# Mini_Power_Supply.net
KiCad netlist of a schematic drawn in EAGLE
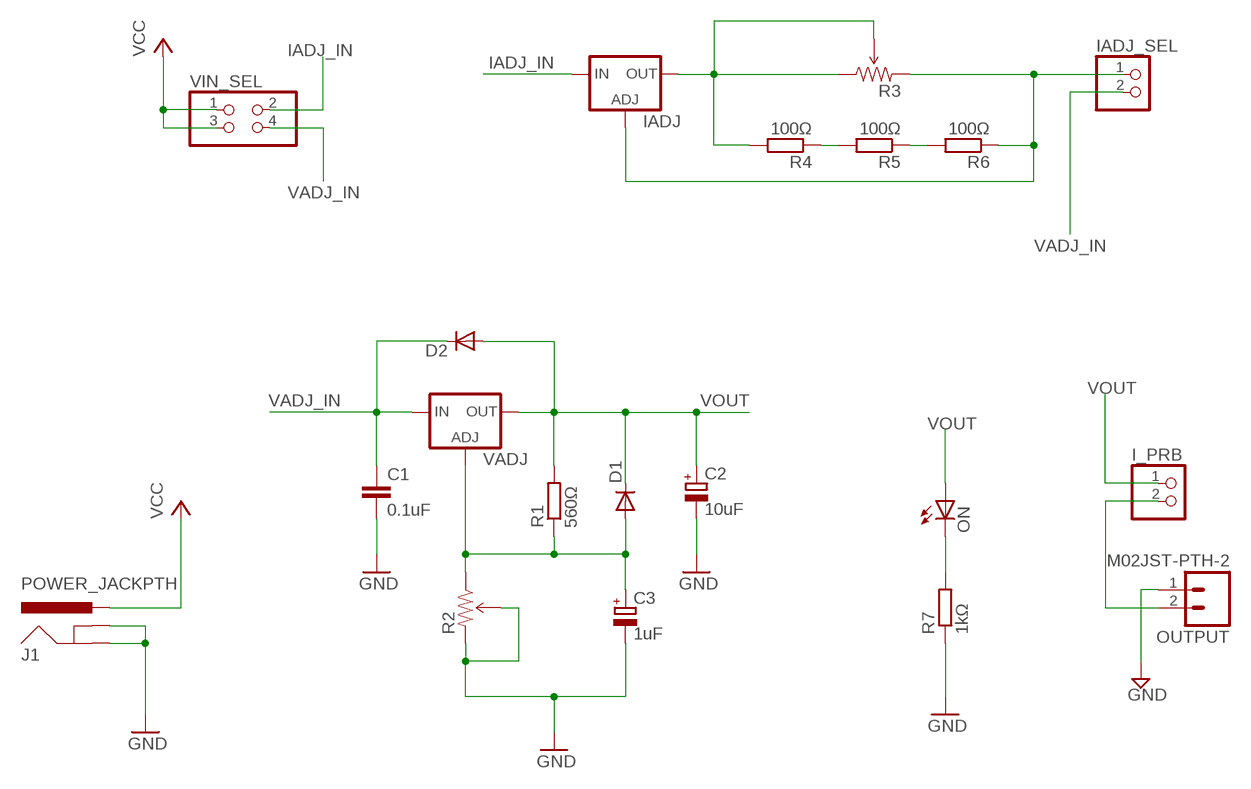
[diagram p0: schematic, sheet 1]

(export (version "E")
  (design (tool "Eeschema 10.0.6"))
  (components
    (comp (ref "C1")
      (value "0.1uF")
      (footprint "eagle-import:C0805")
      (libsource (lib "eagle-import") (part "C-EUC0805"))
    )
    (comp (ref "C2")
      (value "10uF")
      (footprint "eagle-import:E2,5-6")
      (libsource (lib "eagle-import") (part "CPOL-EUE2.5-6"))
    )
    (comp (ref "C3")
      (value "1uF")
      (footprint "eagle-import:E2,5-6")
      (libsource (lib "eagle-import") (part "CPOL-EUE2.5-6"))
    )
    (comp (ref "D1")
      (value "DIODE-SOD323-W")
      (footprint "eagle-import:SOD323-W")
      (libsource (lib "eagle-import") (part "DIODE-SOD323-W"))
    )
    (comp (ref "D2")
      (value "DIODE-SOD323-W")
      (footprint "eagle-import:SOD323-W")
      (libsource (lib "eagle-import") (part "DIODE-SOD323-W"))
    )
    (comp (ref "IADJ")
      (value "LM317TS")
      (footprint "eagle-import:317TS")
      (libsource (lib "eagle-import") (part "LM317TS"))
    )
    (comp (ref "IADJ_SEL")
      (value "PINHD-1X2")
      (footprint "eagle-import:1X02")
      (libsource (lib "eagle-import") (part "PINHD-1X2"))
    )
    (comp (ref "I_PRB")
      (value "PINHD-1X2")
      (footprint "eagle-import:1X02")
      (libsource (lib "eagle-import") (part "PINHD-1X2"))
    )
    (comp (ref "J1")
      (value "POWER_JACKPTH")
      (footprint "eagle-import:POWER_JACK_PTH")
      (libsource (lib "eagle-import") (part "POWER_JACKPTH"))
    )
    (comp (ref "ON")
      (value "LEDCHIPLED_1206")
      (footprint "eagle-import:CHIPLED_1206")
      (libsource (lib "eagle-import") (part "LEDCHIPLED_1206"))
    )
    (comp (ref "OUTPUT")
      (value "M02JST-PTH-2")
      (footprint "eagle-import:JST-2-PTH")
      (libsource (lib "eagle-import") (part "M02JST-PTH-2"))
    )
    (comp (ref "R1")
      (value "560Ω")
      (footprint "eagle-import:R0805")
      (libsource (lib "eagle-import") (part "R-EU_R0805"))
    )
    (comp (ref "R2")
      (value "TRIMPOT-PTH-KNOB")
      (footprint "eagle-import:3386U")
      (libsource (lib "eagle-import") (part "TRIMPOT-PTH-KNOB"))
    )
    (comp (ref "R3")
      (value "TRIMPOT-PTH-KNOB")
      (footprint "eagle-import:3386U")
      (libsource (lib "eagle-import") (part "TRIMPOT-PTH-KNOB"))
    )
    (comp (ref "R4")
      (value "100Ω")
      (footprint "eagle-import:R0805")
      (libsource (lib "eagle-import") (part "R-EU_R0805"))
    )
    (comp (ref "R5")
      (value "100Ω")
      (footprint "eagle-import:R0805")
      (libsource (lib "eagle-import") (part "R-EU_R0805"))
    )
    (comp (ref "R6")
      (value "100Ω")
      (footprint "eagle-import:R0805")
      (libsource (lib "eagle-import") (part "R-EU_R0805"))
    )
    (comp (ref "R7")
      (value "1kΩ")
      (footprint "eagle-import:R0805")
      (libsource (lib "eagle-import") (part "R-EU_R0805"))
    )
    (comp (ref "VADJ")
      (value "LM317TS")
      (footprint "eagle-import:317TS")
      (libsource (lib "eagle-import") (part "LM317TS"))
    )
    (comp (ref "VIN_SEL")
      (value "PINHD-2X2")
      (footprint "eagle-import:2X02")
      (libsource (lib "eagle-import") (part "PINHD-2X2"))
    )
  )
  (nets
    (net (code "1") (name "/IADJ_IN") (class "Default")
      (node (ref "IADJ") (pin "3") (pinfunction "IN_3") (pintype "input"))
      (node (ref "VIN_SEL") (pin "2") (pinfunction "2_2") (pintype "passive"))
    )
    (net (code "2") (name "/VADJ_IN") (class "Default")
      (node (ref "C1") (pin "1") (pinfunction "1_1") (pintype "passive"))
      (node (ref "D2") (pin "C") (pinfunction "C_C") (pintype "passive"))
      (node (ref "IADJ_SEL") (pin "2") (pinfunction "2_2") (pintype "passive"))
      (node (ref "VADJ") (pin "3") (pinfunction "IN_3") (pintype "input"))
      (node (ref "VIN_SEL") (pin "4") (pinfunction "4_4") (pintype "passive"))
    )
    (net (code "3") (name "/VOUT") (class "Default")
      (node (ref "C2") (pin "+") (pinfunction "+_+") (pintype "passive"))
      (node (ref "D1") (pin "C") (pinfunction "C_C") (pintype "passive"))
      (node (ref "D2") (pin "A") (pinfunction "A_A") (pintype "passive"))
      (node (ref "I_PRB") (pin "1") (pinfunction "1_1") (pintype "passive"))
      (node (ref "ON") (pin "A") (pinfunction "A_A") (pintype "passive"))
      (node (ref "R1") (pin "2") (pinfunction "2_2") (pintype "passive"))
      (node (ref "VADJ") (pin "2") (pinfunction "OUT_2") (pintype "passive"))
    )
    (net (code "4") (name "GND") (class "Default")
      (node (ref "C1") (pin "2") (pinfunction "2_2") (pintype "passive"))
      (node (ref "C2") (pin "-") (pinfunction "-_-") (pintype "passive"))
      (node (ref "C3") (pin "-") (pinfunction "-_-") (pintype "passive"))
      (node (ref "J1") (pin "GND") (pinfunction "GND_GND") (pintype "bidirectional"))
      (node (ref "J1") (pin "GNDBREAK") (pinfunction "GNDBREAK_GNDBREAK") (pintype "bidirectional"))
      (node (ref "OUTPUT") (pin "1") (pinfunction "1_1") (pintype "passive"))
      (node (ref "R2") (pin "2") (pinfunction "WIPER_2") (pintype "passive"))
      (node (ref "R2") (pin "3") (pinfunction "CW_3") (pintype "passive"))
      (node (ref "R7") (pin "1") (pinfunction "1_1") (pintype "passive"))
    )
    (net (code "5") (name "Net-(IADJ-ADJ)") (class "Default")
      (node (ref "IADJ") (pin "1") (pinfunction "ADJ_1") (pintype "input"))
      (node (ref "IADJ_SEL") (pin "1") (pinfunction "1_1") (pintype "passive"))
      (node (ref "R3") (pin "3") (pinfunction "CW_3") (pintype "passive"))
      (node (ref "R6") (pin "1") (pinfunction "1_1") (pintype "passive"))
    )
    (net (code "6") (name "Net-(IADJ-OUT)") (class "Default")
      (node (ref "IADJ") (pin "2") (pinfunction "OUT_2") (pintype "passive"))
      (node (ref "R3") (pin "1") (pinfunction "CCW_1") (pintype "passive"))
      (node (ref "R3") (pin "2") (pinfunction "WIPER_2") (pintype "passive"))
      (node (ref "R4") (pin "2") (pinfunction "2_2") (pintype "passive"))
    )
    (net (code "7") (name "Net-(I_PRB-Pad2)") (class "Default")
      (node (ref "I_PRB") (pin "2") (pinfunction "2_2") (pintype "passive"))
      (node (ref "OUTPUT") (pin "2") (pinfunction "2_2") (pintype "passive"))
    )
    (net (code "8") (name "Net-(ON-PadC)") (class "Default")
      (node (ref "ON") (pin "C") (pinfunction "C_C") (pintype "passive"))
      (node (ref "R7") (pin "2") (pinfunction "2_2") (pintype "passive"))
    )
    (net (code "9") (name "Net-(R2-CCW)") (class "Default")
      (node (ref "C3") (pin "+") (pinfunction "+_+") (pintype "passive"))
      (node (ref "D1") (pin "A") (pinfunction "A_A") (pintype "passive"))
      (node (ref "R1") (pin "1") (pinfunction "1_1") (pintype "passive"))
      (node (ref "R2") (pin "1") (pinfunction "CCW_1") (pintype "passive"))
      (node (ref "VADJ") (pin "1") (pinfunction "ADJ_1") (pintype "input"))
    )
    (net (code "10") (name "Net-(R4-Pad1)") (class "Default")
      (node (ref "R4") (pin "1") (pinfunction "1_1") (pintype "passive"))
      (node (ref "R5") (pin "2") (pinfunction "2_2") (pintype "passive"))
    )
    (net (code "11") (name "Net-(R5-Pad1)") (class "Default")
      (node (ref "R5") (pin "1") (pinfunction "1_1") (pintype "passive"))
      (node (ref "R6") (pin "2") (pinfunction "2_2") (pintype "passive"))
    )
    (net (code "12") (name "VCC") (class "Default")
      (node (ref "J1") (pin "PWR") (pinfunction "PWR_PWR") (pintype "bidirectional"))
      (node (ref "VIN_SEL") (pin "1") (pinfunction "1_1") (pintype "passive"))
      (node (ref "VIN_SEL") (pin "3") (pinfunction "3_3") (pintype "passive"))
    )
  )
)
